# Rapide7seg.net
KiCad netlist of a schematic drawn in EAGLE
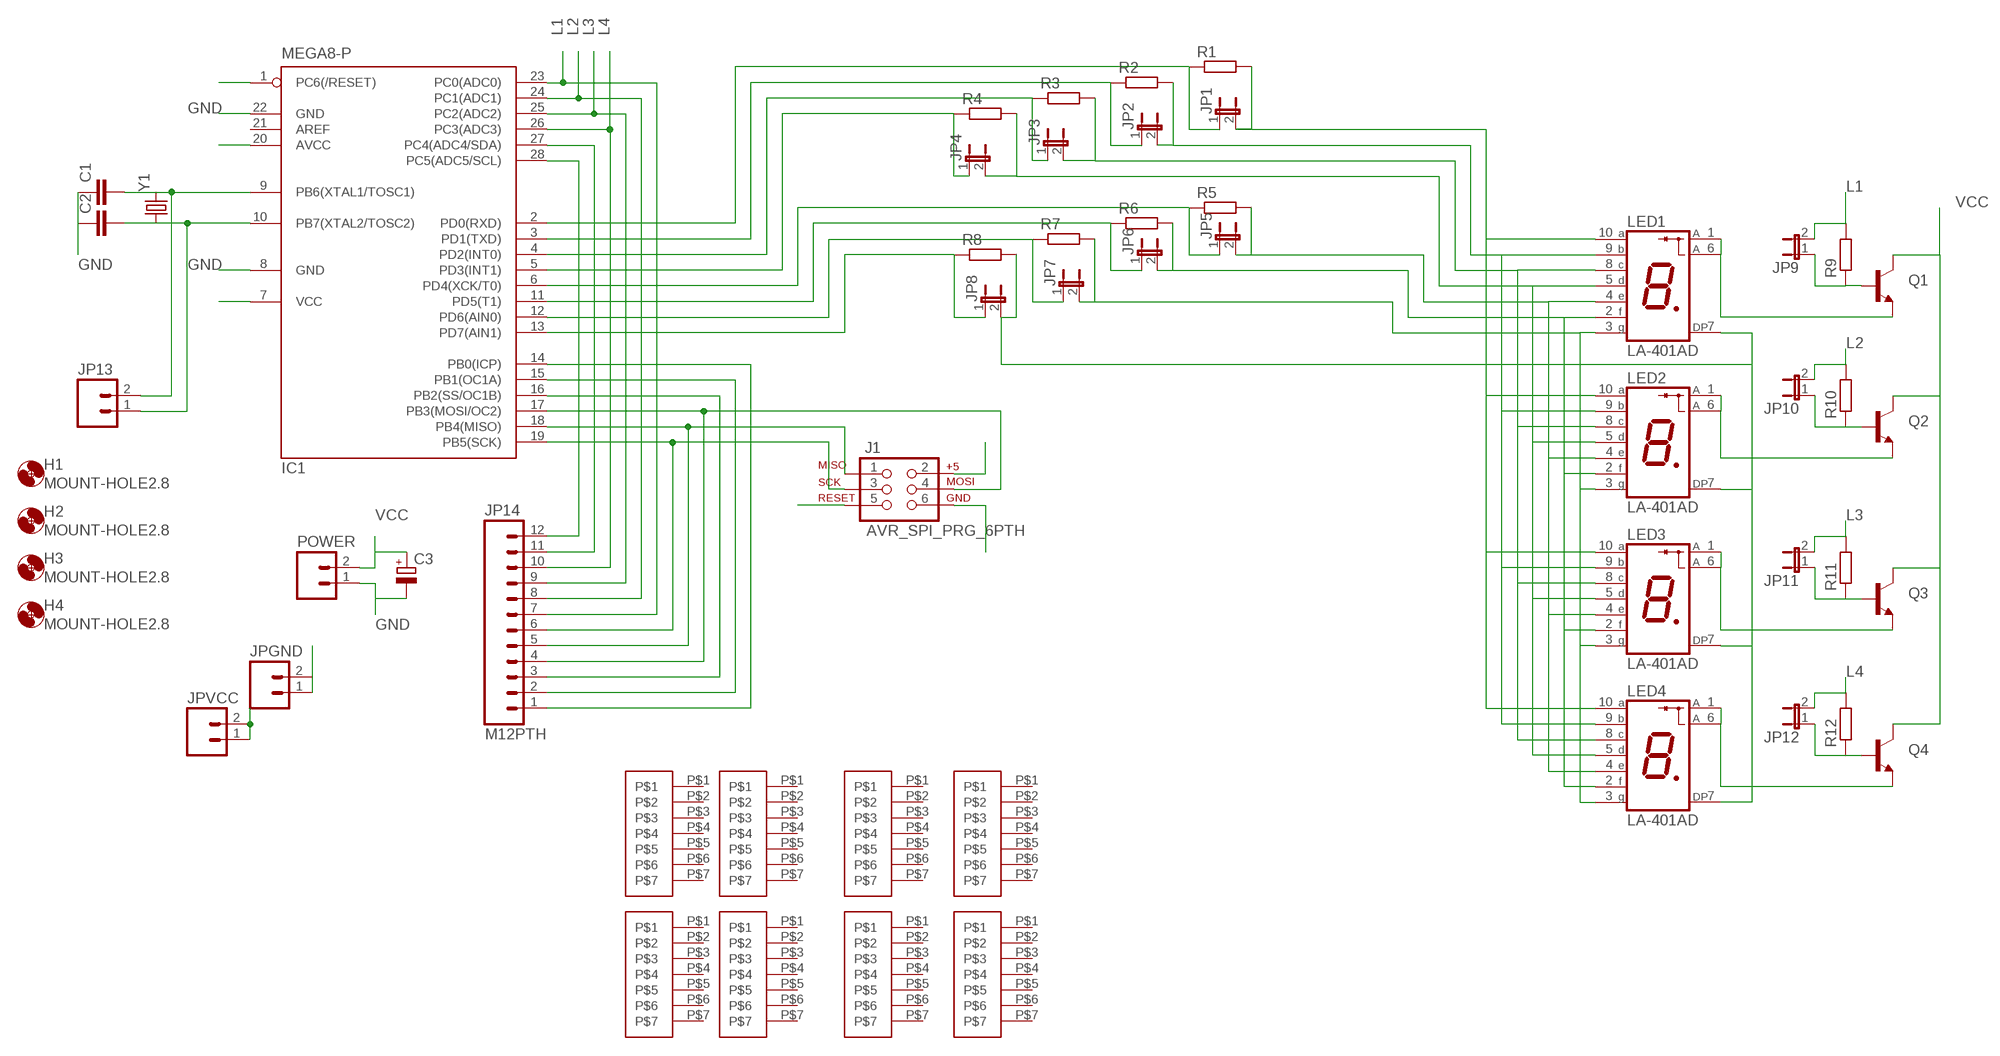
[diagram p0: schematic, sheet 1]

(export (version "E")
  (design (tool "Eeschema 10.0.6"))
  (components
    (comp (ref "C1")
      (value "C-EU025-024X044")
      (footprint "eagle-import:C025-024X044")
      (libsource (lib "eagle-import") (part "C-EU025-024X044"))
    )
    (comp (ref "C2")
      (value "C-EU025-024X044")
      (footprint "eagle-import:C025-024X044")
      (libsource (lib "eagle-import") (part "C-EU025-024X044"))
    )
    (comp (ref "C3")
      (value "CPOL-EUE1.8-4")
      (footprint "eagle-import:E1,8-4")
      (libsource (lib "eagle-import") (part "CPOL-EUE1.8-4"))
    )
    (comp (ref "H1")
      (value "MOUNT-HOLE2.8")
      (footprint "eagle-import:2,8")
      (libsource (lib "eagle-import") (part "MOUNT-HOLE2.8"))
    )
    (comp (ref "H2")
      (value "MOUNT-HOLE2.8")
      (footprint "eagle-import:2,8")
      (libsource (lib "eagle-import") (part "MOUNT-HOLE2.8"))
    )
    (comp (ref "H3")
      (value "MOUNT-HOLE2.8")
      (footprint "eagle-import:2,8")
      (libsource (lib "eagle-import") (part "MOUNT-HOLE2.8"))
    )
    (comp (ref "H4")
      (value "MOUNT-HOLE2.8")
      (footprint "eagle-import:2,8")
      (libsource (lib "eagle-import") (part "MOUNT-HOLE2.8"))
    )
    (comp (ref "IC1")
      (value "MEGA8-P")
      (footprint "eagle-import:DIL28-3")
      (libsource (lib "eagle-import") (part "MEGA8-P"))
    )
    (comp (ref "J1")
      (value "AVR_SPI_PRG_6PTH")
      (footprint "eagle-import:2X3")
      (libsource (lib "eagle-import") (part "AVR_SPI_PRG_6PTH"))
    )
    (comp (ref "JP1")
      (value "JUMPER-2SMD-NO")
      (footprint "eagle-import:SJ_2S-NO")
      (libsource (lib "eagle-import") (part "JUMPER-2SMD-NO"))
    )
    (comp (ref "JP2")
      (value "JUMPER-2SMD-NO")
      (footprint "eagle-import:SJ_2S-NO")
      (libsource (lib "eagle-import") (part "JUMPER-2SMD-NO"))
    )
    (comp (ref "JP3")
      (value "JUMPER-2SMD-NO")
      (footprint "eagle-import:SJ_2S-NO")
      (libsource (lib "eagle-import") (part "JUMPER-2SMD-NO"))
    )
    (comp (ref "JP4")
      (value "JUMPER-2SMD-NO")
      (footprint "eagle-import:SJ_2S-NO")
      (libsource (lib "eagle-import") (part "JUMPER-2SMD-NO"))
    )
    (comp (ref "JP5")
      (value "JUMPER-2SMD-NO")
      (footprint "eagle-import:SJ_2S-NO")
      (libsource (lib "eagle-import") (part "JUMPER-2SMD-NO"))
    )
    (comp (ref "JP6")
      (value "JUMPER-2SMD-NO")
      (footprint "eagle-import:SJ_2S-NO")
      (libsource (lib "eagle-import") (part "JUMPER-2SMD-NO"))
    )
    (comp (ref "JP7")
      (value "JUMPER-2SMD-NO")
      (footprint "eagle-import:SJ_2S-NO")
      (libsource (lib "eagle-import") (part "JUMPER-2SMD-NO"))
    )
    (comp (ref "JP8")
      (value "JUMPER-2SMD-NO")
      (footprint "eagle-import:SJ_2S-NO")
      (libsource (lib "eagle-import") (part "JUMPER-2SMD-NO"))
    )
    (comp (ref "JP9")
      (value "JUMPER-2SMD-NO")
      (footprint "eagle-import:SJ_2S-NO")
      (libsource (lib "eagle-import") (part "JUMPER-2SMD-NO"))
    )
    (comp (ref "JP10")
      (value "JUMPER-2SMD-NO")
      (footprint "eagle-import:SJ_2S-NO")
      (libsource (lib "eagle-import") (part "JUMPER-2SMD-NO"))
    )
    (comp (ref "JP11")
      (value "JUMPER-2SMD-NO")
      (footprint "eagle-import:SJ_2S-NO")
      (libsource (lib "eagle-import") (part "JUMPER-2SMD-NO"))
    )
    (comp (ref "JP12")
      (value "JUMPER-2SMD-NO")
      (footprint "eagle-import:SJ_2S-NO")
      (libsource (lib "eagle-import") (part "JUMPER-2SMD-NO"))
    )
    (comp (ref "JP13")
      (value "M02LOCK")
      (footprint "eagle-import:1X02_LOCK")
      (libsource (lib "eagle-import") (part "M02LOCK"))
    )
    (comp (ref "JP14")
      (value "M12PTH")
      (footprint "eagle-import:1X12")
      (libsource (lib "eagle-import") (part "M12PTH"))
    )
    (comp (ref "JPGND")
      (value "M02PTH")
      (footprint "eagle-import:1X02")
      (libsource (lib "eagle-import") (part "M02PTH"))
    )
    (comp (ref "JPVCC")
      (value "M02PTH")
      (footprint "eagle-import:1X02")
      (libsource (lib "eagle-import") (part "M02PTH"))
    )
    (comp (ref "LED1")
      (value "LA-401AD")
      (footprint "eagle-import:LA-401")
      (libsource (lib "eagle-import") (part "LA-401DA"))
    )
    (comp (ref "LED2")
      (value "LA-401AD")
      (footprint "eagle-import:LA-401")
      (libsource (lib "eagle-import") (part "LA-401DA"))
    )
    (comp (ref "LED3")
      (value "LA-401AD")
      (footprint "eagle-import:LA-401")
      (libsource (lib "eagle-import") (part "LA-401DA"))
    )
    (comp (ref "LED4")
      (value "LA-401AD")
      (footprint "eagle-import:LA-401")
      (libsource (lib "eagle-import") (part "LA-401DA"))
    )
    (comp (ref "POWER")
      (value "M02LOCK_LONGPADS")
      (footprint "eagle-import:1X02_LOCK_LONGPADS")
      (libsource (lib "eagle-import") (part "M02LOCK_LONGPADS"))
    )
    (comp (ref "Q1")
      (value "TRANSISTOR_NPNTO92")
      (footprint "eagle-import:TO-92")
      (libsource (lib "eagle-import") (part "TRANSISTOR_NPNTO92"))
    )
    (comp (ref "Q2")
      (value "TRANSISTOR_NPNTO92")
      (footprint "eagle-import:TO-92")
      (libsource (lib "eagle-import") (part "TRANSISTOR_NPNTO92"))
    )
    (comp (ref "Q3")
      (value "TRANSISTOR_NPNTO92")
      (footprint "eagle-import:TO-92")
      (libsource (lib "eagle-import") (part "TRANSISTOR_NPNTO92"))
    )
    (comp (ref "Q4")
      (value "TRANSISTOR_NPNTO92")
      (footprint "eagle-import:TO-92")
      (libsource (lib "eagle-import") (part "TRANSISTOR_NPNTO92"))
    )
    (comp (ref "R1")
      (value "R-EU_0204/7")
      (footprint "eagle-import:0204_7")
      (libsource (lib "eagle-import") (part "R-EU_0204/7"))
    )
    (comp (ref "R2")
      (value "R-EU_0204/7")
      (footprint "eagle-import:0204_7")
      (libsource (lib "eagle-import") (part "R-EU_0204/7"))
    )
    (comp (ref "R3")
      (value "R-EU_0204/7")
      (footprint "eagle-import:0204_7")
      (libsource (lib "eagle-import") (part "R-EU_0204/7"))
    )
    (comp (ref "R4")
      (value "R-EU_0204/7")
      (footprint "eagle-import:0204_7")
      (libsource (lib "eagle-import") (part "R-EU_0204/7"))
    )
    (comp (ref "R5")
      (value "R-EU_0204/7")
      (footprint "eagle-import:0204_7")
      (libsource (lib "eagle-import") (part "R-EU_0204/7"))
    )
    (comp (ref "R6")
      (value "R-EU_0204/7")
      (footprint "eagle-import:0204_7")
      (libsource (lib "eagle-import") (part "R-EU_0204/7"))
    )
    (comp (ref "R7")
      (value "R-EU_0204/7")
      (footprint "eagle-import:0204_7")
      (libsource (lib "eagle-import") (part "R-EU_0204/7"))
    )
    (comp (ref "R8")
      (value "R-EU_0204/7")
      (footprint "eagle-import:0204_7")
      (libsource (lib "eagle-import") (part "R-EU_0204/7"))
    )
    (comp (ref "R9")
      (value "R-EU_0204/7")
      (footprint "eagle-import:0204_7")
      (libsource (lib "eagle-import") (part "R-EU_0204/7"))
    )
    (comp (ref "R10")
      (value "R-EU_0204/7")
      (footprint "eagle-import:0204_7")
      (libsource (lib "eagle-import") (part "R-EU_0204/7"))
    )
    (comp (ref "R11")
      (value "R-EU_0204/7")
      (footprint "eagle-import:0204_7")
      (libsource (lib "eagle-import") (part "R-EU_0204/7"))
    )
    (comp (ref "R12")
      (value "R-EU_0204/7")
      (footprint "eagle-import:0204_7")
      (libsource (lib "eagle-import") (part "R-EU_0204/7"))
    )
    (comp (ref "U$1")
      (value "M7_NOSILK")
      (footprint "eagle-import:M7_NOSILK")
      (libsource (lib "eagle-import") (part "M7_NOSILK"))
    )
    (comp (ref "U$2")
      (value "M7_NOSILK")
      (footprint "eagle-import:M7_NOSILK")
      (libsource (lib "eagle-import") (part "M7_NOSILK"))
    )
    (comp (ref "U$3")
      (value "M7_NOSILK")
      (footprint "eagle-import:M7_NOSILK")
      (libsource (lib "eagle-import") (part "M7_NOSILK"))
    )
    (comp (ref "U$4")
      (value "M7_NOSILK")
      (footprint "eagle-import:M7_NOSILK")
      (libsource (lib "eagle-import") (part "M7_NOSILK"))
    )
    (comp (ref "U$5")
      (value "M7_NOSILK")
      (footprint "eagle-import:M7_NOSILK")
      (libsource (lib "eagle-import") (part "M7_NOSILK"))
    )
    (comp (ref "U$6")
      (value "M7_NOSILK")
      (footprint "eagle-import:M7_NOSILK")
      (libsource (lib "eagle-import") (part "M7_NOSILK"))
    )
    (comp (ref "U$7")
      (value "M7_NOSILK")
      (footprint "eagle-import:M7_NOSILK")
      (libsource (lib "eagle-import") (part "M7_NOSILK"))
    )
    (comp (ref "U$8")
      (value "M7_NOSILK")
      (footprint "eagle-import:M7_NOSILK")
      (libsource (lib "eagle-import") (part "M7_NOSILK"))
    )
    (comp (ref "Y1")
      (value "CRYSTALHC49UV")
      (footprint "eagle-import:HC49U-V")
      (libsource (lib "eagle-import") (part "CRYSTALHC49UV"))
    )
  )
  (nets
    (net (code "1") (name "/GND") (class "Default")
      (node (ref "C1") (pin "1") (pinfunction "1_1") (pintype "passive"))
      (node (ref "C2") (pin "1") (pinfunction "1_1") (pintype "passive"))
      (node (ref "C3") (pin "-") (pinfunction "-_-") (pintype "passive"))
      (node (ref "IC1") (pin "22") (pinfunction "GND_22") (pintype "power_in"))
      (node (ref "IC1") (pin "8") (pinfunction "GND_8") (pintype "power_in"))
      (node (ref "J1") (pin "6") (pinfunction "6_6") (pintype "passive"))
      (node (ref "JPGND") (pin "1") (pinfunction "1_1") (pintype "passive"))
      (node (ref "JPGND") (pin "2") (pinfunction "2_2") (pintype "passive"))
      (node (ref "POWER") (pin "1") (pinfunction "1_1") (pintype "passive"))
    )
    (net (code "2") (name "/L1") (class "Default")
      (node (ref "IC1") (pin "23") (pinfunction "PC0(ADC0)_23") (pintype "bidirectional"))
      (node (ref "JP14") (pin "7") (pinfunction "7_7") (pintype "passive"))
      (node (ref "JP9") (pin "2") (pinfunction "2_2") (pintype "passive"))
      (node (ref "R9") (pin "2") (pinfunction "2_2") (pintype "passive"))
    )
    (net (code "3") (name "/L2") (class "Default")
      (node (ref "IC1") (pin "24") (pinfunction "PC1(ADC1)_24") (pintype "bidirectional"))
      (node (ref "JP10") (pin "2") (pinfunction "2_2") (pintype "passive"))
      (node (ref "JP14") (pin "8") (pinfunction "8_8") (pintype "passive"))
      (node (ref "R10") (pin "2") (pinfunction "2_2") (pintype "passive"))
    )
    (net (code "4") (name "/L3") (class "Default")
      (node (ref "IC1") (pin "25") (pinfunction "PC2(ADC2)_25") (pintype "bidirectional"))
      (node (ref "JP11") (pin "2") (pinfunction "2_2") (pintype "passive"))
      (node (ref "JP14") (pin "9") (pinfunction "9_9") (pintype "passive"))
      (node (ref "R11") (pin "2") (pinfunction "2_2") (pintype "passive"))
    )
    (net (code "5") (name "/L4") (class "Default")
      (node (ref "IC1") (pin "26") (pinfunction "PC3(ADC3)_26") (pintype "bidirectional"))
      (node (ref "JP12") (pin "2") (pinfunction "2_2") (pintype "passive"))
      (node (ref "JP14") (pin "10") (pinfunction "10_10") (pintype "passive"))
      (node (ref "R12") (pin "2") (pinfunction "2_2") (pintype "passive"))
    )
    (net (code "6") (name "/UCRESET") (class "Default")
      (node (ref "IC1") (pin "1") (pinfunction "PC6(/RESET)_1") (pintype "bidirectional"))
      (node (ref "J1") (pin "5") (pinfunction "5_5") (pintype "passive"))
    )
    (net (code "7") (name "/VCC") (class "Default")
      (node (ref "C3") (pin "+") (pinfunction "+_+") (pintype "passive"))
      (node (ref "IC1") (pin "20") (pinfunction "AVCC_20") (pintype "power_in"))
      (node (ref "IC1") (pin "7") (pinfunction "VCC_7") (pintype "power_in"))
      (node (ref "J1") (pin "2") (pinfunction "2_2") (pintype "passive"))
      (node (ref "JPVCC") (pin "1") (pinfunction "1_1") (pintype "passive"))
      (node (ref "JPVCC") (pin "2") (pinfunction "2_2") (pintype "passive"))
      (node (ref "POWER") (pin "2") (pinfunction "2_2") (pintype "passive"))
      (node (ref "Q1") (pin "3") (pinfunction "C_3") (pintype "passive"))
      (node (ref "Q2") (pin "3") (pinfunction "C_3") (pintype "passive"))
      (node (ref "Q3") (pin "3") (pinfunction "C_3") (pintype "passive"))
      (node (ref "Q4") (pin "3") (pinfunction "C_3") (pintype "passive"))
    )
    (net (code "8") (name "Net-(IC1-PB0(ICP))") (class "Default")
      (node (ref "IC1") (pin "14") (pinfunction "PB0(ICP)_14") (pintype "bidirectional"))
      (node (ref "JP14") (pin "1") (pinfunction "1_1") (pintype "passive"))
    )
    (net (code "9") (name "Net-(IC1-PB1(OC1A))") (class "Default")
      (node (ref "IC1") (pin "15") (pinfunction "PB1(OC1A)_15") (pintype "bidirectional"))
      (node (ref "JP14") (pin "2") (pinfunction "2_2") (pintype "passive"))
    )
    (net (code "10") (name "Net-(IC1-PB2(SS{slash}OC1B))") (class "Default")
      (node (ref "IC1") (pin "16") (pinfunction "PB2(SS/OC1B)_16") (pintype "bidirectional"))
      (node (ref "JP14") (pin "3") (pinfunction "3_3") (pintype "passive"))
    )
    (net (code "11") (name "Net-(IC1-PB3(MOSI{slash}OC2))") (class "Default")
      (node (ref "IC1") (pin "17") (pinfunction "PB3(MOSI/OC2)_17") (pintype "bidirectional"))
      (node (ref "J1") (pin "4") (pinfunction "4_4") (pintype "passive"))
      (node (ref "JP14") (pin "4") (pinfunction "4_4") (pintype "passive"))
    )
    (net (code "12") (name "Net-(IC1-PB4(MISO))") (class "Default")
      (node (ref "IC1") (pin "18") (pinfunction "PB4(MISO)_18") (pintype "bidirectional"))
      (node (ref "J1") (pin "1") (pinfunction "1_1") (pintype "passive"))
      (node (ref "JP14") (pin "5") (pinfunction "5_5") (pintype "passive"))
    )
    (net (code "13") (name "Net-(IC1-PB5(SCK))") (class "Default")
      (node (ref "IC1") (pin "19") (pinfunction "PB5(SCK)_19") (pintype "bidirectional"))
      (node (ref "J1") (pin "3") (pinfunction "3_3") (pintype "passive"))
      (node (ref "JP14") (pin "6") (pinfunction "6_6") (pintype "passive"))
    )
    (net (code "14") (name "Net-(IC1-PB6(XTAL1{slash}TOSC1))") (class "Default")
      (node (ref "C1") (pin "2") (pinfunction "2_2") (pintype "passive"))
      (node (ref "IC1") (pin "9") (pinfunction "PB6(XTAL1/TOSC1)_9") (pintype "bidirectional"))
      (node (ref "JP13") (pin "2") (pinfunction "2_2") (pintype "passive"))
      (node (ref "Y1") (pin "2") (pinfunction "2_2") (pintype "passive"))
    )
    (net (code "15") (name "Net-(IC1-PB7(XTAL2{slash}TOSC2))") (class "Default")
      (node (ref "C2") (pin "2") (pinfunction "2_2") (pintype "passive"))
      (node (ref "IC1") (pin "10") (pinfunction "PB7(XTAL2/TOSC2)_10") (pintype "bidirectional"))
      (node (ref "JP13") (pin "1") (pinfunction "1_1") (pintype "passive"))
      (node (ref "Y1") (pin "1") (pinfunction "1_1") (pintype "passive"))
    )
    (net (code "16") (name "Net-(IC1-PC4(ADC4{slash}SDA))") (class "Default")
      (node (ref "IC1") (pin "27") (pinfunction "PC4(ADC4/SDA)_27") (pintype "bidirectional"))
      (node (ref "JP14") (pin "11") (pinfunction "11_11") (pintype "passive"))
    )
    (net (code "17") (name "Net-(IC1-PC5(ADC5{slash}SCL))") (class "Default")
      (node (ref "IC1") (pin "28") (pinfunction "PC5(ADC5/SCL)_28") (pintype "bidirectional"))
      (node (ref "JP14") (pin "12") (pinfunction "12_12") (pintype "passive"))
    )
    (net (code "18") (name "Net-(IC1-PD0(RXD))") (class "Default")
      (node (ref "IC1") (pin "2") (pinfunction "PD0(RXD)_2") (pintype "bidirectional"))
      (node (ref "JP1") (pin "1") (pinfunction "1_1") (pintype "passive"))
      (node (ref "R1") (pin "1") (pinfunction "1_1") (pintype "passive"))
    )
    (net (code "19") (name "Net-(IC1-PD1(TXD))") (class "Default")
      (node (ref "IC1") (pin "3") (pinfunction "PD1(TXD)_3") (pintype "bidirectional"))
      (node (ref "JP2") (pin "1") (pinfunction "1_1") (pintype "passive"))
      (node (ref "R2") (pin "1") (pinfunction "1_1") (pintype "passive"))
    )
    (net (code "20") (name "Net-(IC1-PD2(INT0))") (class "Default")
      (node (ref "IC1") (pin "4") (pinfunction "PD2(INT0)_4") (pintype "bidirectional"))
      (node (ref "JP3") (pin "1") (pinfunction "1_1") (pintype "passive"))
      (node (ref "R3") (pin "1") (pinfunction "1_1") (pintype "passive"))
    )
    (net (code "21") (name "Net-(IC1-PD3(INT1))") (class "Default")
      (node (ref "IC1") (pin "5") (pinfunction "PD3(INT1)_5") (pintype "bidirectional"))
      (node (ref "JP4") (pin "1") (pinfunction "1_1") (pintype "passive"))
      (node (ref "R4") (pin "1") (pinfunction "1_1") (pintype "passive"))
    )
    (net (code "22") (name "Net-(IC1-PD4(XCK{slash}T0))") (class "Default")
      (node (ref "IC1") (pin "6") (pinfunction "PD4(XCK/T0)_6") (pintype "bidirectional"))
      (node (ref "JP5") (pin "1") (pinfunction "1_1") (pintype "passive"))
      (node (ref "R5") (pin "1") (pinfunction "1_1") (pintype "passive"))
    )
    (net (code "23") (name "Net-(IC1-PD5(T1))") (class "Default")
      (node (ref "IC1") (pin "11") (pinfunction "PD5(T1)_11") (pintype "bidirectional"))
      (node (ref "JP6") (pin "1") (pinfunction "1_1") (pintype "passive"))
      (node (ref "R6") (pin "1") (pinfunction "1_1") (pintype "passive"))
    )
    (net (code "24") (name "Net-(IC1-PD6(AIN0))") (class "Default")
      (node (ref "IC1") (pin "12") (pinfunction "PD6(AIN0)_12") (pintype "bidirectional"))
      (node (ref "JP7") (pin "1") (pinfunction "1_1") (pintype "passive"))
      (node (ref "R7") (pin "1") (pinfunction "1_1") (pintype "passive"))
    )
    (net (code "25") (name "Net-(IC1-PD7(AIN1))") (class "Default")
      (node (ref "IC1") (pin "13") (pinfunction "PD7(AIN1)_13") (pintype "bidirectional"))
      (node (ref "JP8") (pin "1") (pinfunction "1_1") (pintype "passive"))
      (node (ref "R8") (pin "1") (pinfunction "1_1") (pintype "passive"))
    )
    (net (code "26") (name "Net-(JP1-Pad2)") (class "Default")
      (node (ref "JP1") (pin "2") (pinfunction "2_2") (pintype "passive"))
      (node (ref "LED1") (pin "10") (pinfunction "A_10") (pintype "passive"))
      (node (ref "LED2") (pin "10") (pinfunction "A_10") (pintype "passive"))
      (node (ref "LED3") (pin "10") (pinfunction "A_10") (pintype "passive"))
      (node (ref "LED4") (pin "10") (pinfunction "A_10") (pintype "passive"))
      (node (ref "R1") (pin "2") (pinfunction "2_2") (pintype "passive"))
    )
    (net (code "27") (name "Net-(LED1-B)") (class "Default")
      (node (ref "JP2") (pin "2") (pinfunction "2_2") (pintype "passive"))
      (node (ref "LED1") (pin "9") (pinfunction "B_9") (pintype "passive"))
      (node (ref "LED2") (pin "9") (pinfunction "B_9") (pintype "passive"))
      (node (ref "LED3") (pin "9") (pinfunction "B_9") (pintype "passive"))
      (node (ref "LED4") (pin "9") (pinfunction "B_9") (pintype "passive"))
      (node (ref "R2") (pin "2") (pinfunction "2_2") (pintype "passive"))
    )
    (net (code "28") (name "Net-(LED1-C)") (class "Default")
      (node (ref "JP3") (pin "2") (pinfunction "2_2") (pintype "passive"))
      (node (ref "LED1") (pin "8") (pinfunction "C_8") (pintype "passive"))
      (node (ref "LED2") (pin "8") (pinfunction "C_8") (pintype "passive"))
      (node (ref "LED3") (pin "8") (pinfunction "C_8") (pintype "passive"))
      (node (ref "LED4") (pin "8") (pinfunction "C_8") (pintype "passive"))
      (node (ref "R3") (pin "2") (pinfunction "2_2") (pintype "passive"))
    )
    (net (code "29") (name "Net-(LED1-D)") (class "Default")
      (node (ref "JP4") (pin "2") (pinfunction "2_2") (pintype "passive"))
      (node (ref "LED1") (pin "5") (pinfunction "D_5") (pintype "passive"))
      (node (ref "LED2") (pin "5") (pinfunction "D_5") (pintype "passive"))
      (node (ref "LED3") (pin "5") (pinfunction "D_5") (pintype "passive"))
      (node (ref "LED4") (pin "5") (pinfunction "D_5") (pintype "passive"))
      (node (ref "R4") (pin "2") (pinfunction "2_2") (pintype "passive"))
    )
    (net (code "30") (name "Net-(LED1-DP)") (class "Default")
      (node (ref "JP8") (pin "2") (pinfunction "2_2") (pintype "passive"))
      (node (ref "LED1") (pin "7") (pinfunction "DP_7") (pintype "passive"))
      (node (ref "LED2") (pin "7") (pinfunction "DP_7") (pintype "passive"))
      (node (ref "LED3") (pin "7") (pinfunction "DP_7") (pintype "passive"))
      (node (ref "LED4") (pin "7") (pinfunction "DP_7") (pintype "passive"))
      (node (ref "R8") (pin "2") (pinfunction "2_2") (pintype "passive"))
    )
    (net (code "31") (name "Net-(LED1-E)") (class "Default")
      (node (ref "JP5") (pin "2") (pinfunction "2_2") (pintype "passive"))
      (node (ref "LED1") (pin "4") (pinfunction "E_4") (pintype "passive"))
      (node (ref "LED2") (pin "4") (pinfunction "E_4") (pintype "passive"))
      (node (ref "LED3") (pin "4") (pinfunction "E_4") (pintype "passive"))
      (node (ref "LED4") (pin "4") (pinfunction "E_4") (pintype "passive"))
      (node (ref "R5") (pin "2") (pinfunction "2_2") (pintype "passive"))
    )
    (net (code "32") (name "Net-(LED1-F)") (class "Default")
      (node (ref "JP6") (pin "2") (pinfunction "2_2") (pintype "passive"))
      (node (ref "LED1") (pin "2") (pinfunction "F_2") (pintype "passive"))
      (node (ref "LED2") (pin "2") (pinfunction "F_2") (pintype "passive"))
      (node (ref "LED3") (pin "2") (pinfunction "F_2") (pintype "passive"))
      (node (ref "LED4") (pin "2") (pinfunction "F_2") (pintype "passive"))
      (node (ref "R6") (pin "2") (pinfunction "2_2") (pintype "passive"))
    )
    (net (code "33") (name "Net-(LED1-G)") (class "Default")
      (node (ref "JP7") (pin "2") (pinfunction "2_2") (pintype "passive"))
      (node (ref "LED1") (pin "3") (pinfunction "G_3") (pintype "passive"))
      (node (ref "LED2") (pin "3") (pinfunction "G_3") (pintype "passive"))
      (node (ref "LED3") (pin "3") (pinfunction "G_3") (pintype "passive"))
      (node (ref "LED4") (pin "3") (pinfunction "G_3") (pintype "passive"))
      (node (ref "R7") (pin "2") (pinfunction "2_2") (pintype "passive"))
    )
    (net (code "34") (name "Net-(Q1-B)") (class "Default")
      (node (ref "JP9") (pin "1") (pinfunction "1_1") (pintype "passive"))
      (node (ref "Q1") (pin "2") (pinfunction "B_2") (pintype "passive"))
      (node (ref "R9") (pin "1") (pinfunction "1_1") (pintype "passive"))
    )
    (net (code "35") (name "Net-(Q1-E)") (class "Default")
      (node (ref "LED1") (pin "1") (pinfunction "A_1") (pintype "passive"))
      (node (ref "LED1") (pin "6") (pinfunction "A_6") (pintype "passive"))
      (node (ref "Q1") (pin "1") (pinfunction "E_1") (pintype "passive"))
    )
    (net (code "36") (name "Net-(Q2-B)") (class "Default")
      (node (ref "JP10") (pin "1") (pinfunction "1_1") (pintype "passive"))
      (node (ref "Q2") (pin "2") (pinfunction "B_2") (pintype "passive"))
      (node (ref "R10") (pin "1") (pinfunction "1_1") (pintype "passive"))
    )
    (net (code "37") (name "Net-(Q2-E)") (class "Default")
      (node (ref "LED2") (pin "1") (pinfunction "A_1") (pintype "passive"))
      (node (ref "LED2") (pin "6") (pinfunction "A_6") (pintype "passive"))
      (node (ref "Q2") (pin "1") (pinfunction "E_1") (pintype "passive"))
    )
    (net (code "38") (name "Net-(Q3-B)") (class "Default")
      (node (ref "JP11") (pin "1") (pinfunction "1_1") (pintype "passive"))
      (node (ref "Q3") (pin "2") (pinfunction "B_2") (pintype "passive"))
      (node (ref "R11") (pin "1") (pinfunction "1_1") (pintype "passive"))
    )
    (net (code "39") (name "Net-(Q3-E)") (class "Default")
      (node (ref "LED3") (pin "1") (pinfunction "A_1") (pintype "passive"))
      (node (ref "LED3") (pin "6") (pinfunction "A_6") (pintype "passive"))
      (node (ref "Q3") (pin "1") (pinfunction "E_1") (pintype "passive"))
    )
    (net (code "40") (name "Net-(Q4-B)") (class "Default")
      (node (ref "JP12") (pin "1") (pinfunction "1_1") (pintype "passive"))
      (node (ref "Q4") (pin "2") (pinfunction "B_2") (pintype "passive"))
      (node (ref "R12") (pin "1") (pinfunction "1_1") (pintype "passive"))
    )
    (net (code "41") (name "Net-(Q4-E)") (class "Default")
      (node (ref "LED4") (pin "1") (pinfunction "A_1") (pintype "passive"))
      (node (ref "LED4") (pin "6") (pinfunction "A_6") (pintype "passive"))
      (node (ref "Q4") (pin "1") (pinfunction "E_1") (pintype "passive"))
    )
    (net (code "42") (name "unconnected-(IC1-AREF-Pad21)") (class "Default")
      (node (ref "IC1") (pin "21") (pinfunction "AREF_21") (pintype "passive"))
    )
    (net (code "43") (name "unconnected-(U$1-PadP$1)") (class "Default")
      (node (ref "U$1") (pin "P$1") (pinfunction "P$1_P$1") (pintype "bidirectional"))
    )
    (net (code "44") (name "unconnected-(U$1-PadP$2)") (class "Default")
      (node (ref "U$1") (pin "P$2") (pinfunction "P$2_P$2") (pintype "bidirectional"))
    )
    (net (code "45") (name "unconnected-(U$1-PadP$3)") (class "Default")
      (node (ref "U$1") (pin "P$3") (pinfunction "P$3_P$3") (pintype "bidirectional"))
    )
    (net (code "46") (name "unconnected-(U$1-PadP$4)") (class "Default")
      (node (ref "U$1") (pin "P$4") (pinfunction "P$4_P$4") (pintype "bidirectional"))
    )
    (net (code "47") (name "unconnected-(U$1-PadP$5)") (class "Default")
      (node (ref "U$1") (pin "P$5") (pinfunction "P$5_P$5") (pintype "bidirectional"))
    )
    (net (code "48") (name "unconnected-(U$1-PadP$6)") (class "Default")
      (node (ref "U$1") (pin "P$6") (pinfunction "P$6_P$6") (pintype "bidirectional"))
    )
    (net (code "49") (name "unconnected-(U$1-PadP$7)") (class "Default")
      (node (ref "U$1") (pin "P$7") (pinfunction "P$7_P$7") (pintype "bidirectional"))
    )
    (net (code "50") (name "unconnected-(U$2-PadP$1)") (class "Default")
      (node (ref "U$2") (pin "P$1") (pinfunction "P$1_P$1") (pintype "bidirectional"))
    )
    (net (code "51") (name "unconnected-(U$2-PadP$2)") (class "Default")
      (node (ref "U$2") (pin "P$2") (pinfunction "P$2_P$2") (pintype "bidirectional"))
    )
    (net (code "52") (name "unconnected-(U$2-PadP$3)") (class "Default")
      (node (ref "U$2") (pin "P$3") (pinfunction "P$3_P$3") (pintype "bidirectional"))
    )
    (net (code "53") (name "unconnected-(U$2-PadP$4)") (class "Default")
      (node (ref "U$2") (pin "P$4") (pinfunction "P$4_P$4") (pintype "bidirectional"))
    )
    (net (code "54") (name "unconnected-(U$2-PadP$5)") (class "Default")
      (node (ref "U$2") (pin "P$5") (pinfunction "P$5_P$5") (pintype "bidirectional"))
    )
    (net (code "55") (name "unconnected-(U$2-PadP$6)") (class "Default")
      (node (ref "U$2") (pin "P$6") (pinfunction "P$6_P$6") (pintype "bidirectional"))
    )
    (net (code "56") (name "unconnected-(U$2-PadP$7)") (class "Default")
      (node (ref "U$2") (pin "P$7") (pinfunction "P$7_P$7") (pintype "bidirectional"))
    )
    (net (code "57") (name "unconnected-(U$3-PadP$1)") (class "Default")
      (node (ref "U$3") (pin "P$1") (pinfunction "P$1_P$1") (pintype "bidirectional"))
    )
    (net (code "58") (name "unconnected-(U$3-PadP$2)") (class "Default")
      (node (ref "U$3") (pin "P$2") (pinfunction "P$2_P$2") (pintype "bidirectional"))
    )
    (net (code "59") (name "unconnected-(U$3-PadP$3)") (class "Default")
      (node (ref "U$3") (pin "P$3") (pinfunction "P$3_P$3") (pintype "bidirectional"))
    )
    (net (code "60") (name "unconnected-(U$3-PadP$4)") (class "Default")
      (node (ref "U$3") (pin "P$4") (pinfunction "P$4_P$4") (pintype "bidirectional"))
    )
    (net (code "61") (name "unconnected-(U$3-PadP$5)") (class "Default")
      (node (ref "U$3") (pin "P$5") (pinfunction "P$5_P$5") (pintype "bidirectional"))
    )
    (net (code "62") (name "unconnected-(U$3-PadP$6)") (class "Default")
      (node (ref "U$3") (pin "P$6") (pinfunction "P$6_P$6") (pintype "bidirectional"))
    )
    (net (code "63") (name "unconnected-(U$3-PadP$7)") (class "Default")
      (node (ref "U$3") (pin "P$7") (pinfunction "P$7_P$7") (pintype "bidirectional"))
    )
    (net (code "64") (name "unconnected-(U$4-PadP$1)") (class "Default")
      (node (ref "U$4") (pin "P$1") (pinfunction "P$1_P$1") (pintype "bidirectional"))
    )
    (net (code "65") (name "unconnected-(U$4-PadP$2)") (class "Default")
      (node (ref "U$4") (pin "P$2") (pinfunction "P$2_P$2") (pintype "bidirectional"))
    )
    (net (code "66") (name "unconnected-(U$4-PadP$3)") (class "Default")
      (node (ref "U$4") (pin "P$3") (pinfunction "P$3_P$3") (pintype "bidirectional"))
    )
    (net (code "67") (name "unconnected-(U$4-PadP$4)") (class "Default")
      (node (ref "U$4") (pin "P$4") (pinfunction "P$4_P$4") (pintype "bidirectional"))
    )
    (net (code "68") (name "unconnected-(U$4-PadP$5)") (class "Default")
      (node (ref "U$4") (pin "P$5") (pinfunction "P$5_P$5") (pintype "bidirectional"))
    )
    (net (code "69") (name "unconnected-(U$4-PadP$6)") (class "Default")
      (node (ref "U$4") (pin "P$6") (pinfunction "P$6_P$6") (pintype "bidirectional"))
    )
    (net (code "70") (name "unconnected-(U$4-PadP$7)") (class "Default")
      (node (ref "U$4") (pin "P$7") (pinfunction "P$7_P$7") (pintype "bidirectional"))
    )
    (net (code "71") (name "unconnected-(U$5-PadP$1)") (class "Default")
      (node (ref "U$5") (pin "P$1") (pinfunction "P$1_P$1") (pintype "bidirectional"))
    )
    (net (code "72") (name "unconnected-(U$5-PadP$2)") (class "Default")
      (node (ref "U$5") (pin "P$2") (pinfunction "P$2_P$2") (pintype "bidirectional"))
    )
    (net (code "73") (name "unconnected-(U$5-PadP$3)") (class "Default")
      (node (ref "U$5") (pin "P$3") (pinfunction "P$3_P$3") (pintype "bidirectional"))
    )
    (net (code "74") (name "unconnected-(U$5-PadP$4)") (class "Default")
      (node (ref "U$5") (pin "P$4") (pinfunction "P$4_P$4") (pintype "bidirectional"))
    )
    (net (code "75") (name "unconnected-(U$5-PadP$5)") (class "Default")
      (node (ref "U$5") (pin "P$5") (pinfunction "P$5_P$5") (pintype "bidirectional"))
    )
    (net (code "76") (name "unconnected-(U$5-PadP$6)") (class "Default")
      (node (ref "U$5") (pin "P$6") (pinfunction "P$6_P$6") (pintype "bidirectional"))
    )
    (net (code "77") (name "unconnected-(U$5-PadP$7)") (class "Default")
      (node (ref "U$5") (pin "P$7") (pinfunction "P$7_P$7") (pintype "bidirectional"))
    )
    (net (code "78") (name "unconnected-(U$6-PadP$1)") (class "Default")
      (node (ref "U$6") (pin "P$1") (pinfunction "P$1_P$1") (pintype "bidirectional"))
    )
    (net (code "79") (name "unconnected-(U$6-PadP$2)") (class "Default")
      (node (ref "U$6") (pin "P$2") (pinfunction "P$2_P$2") (pintype "bidirectional"))
    )
    (net (code "80") (name "unconnected-(U$6-PadP$3)") (class "Default")
      (node (ref "U$6") (pin "P$3") (pinfunction "P$3_P$3") (pintype "bidirectional"))
    )
    (net (code "81") (name "unconnected-(U$6-PadP$4)") (class "Default")
      (node (ref "U$6") (pin "P$4") (pinfunction "P$4_P$4") (pintype "bidirectional"))
    )
    (net (code "82") (name "unconnected-(U$6-PadP$5)") (class "Default")
      (node (ref "U$6") (pin "P$5") (pinfunction "P$5_P$5") (pintype "bidirectional"))
    )
    (net (code "83") (name "unconnected-(U$6-PadP$6)") (class "Default")
      (node (ref "U$6") (pin "P$6") (pinfunction "P$6_P$6") (pintype "bidirectional"))
    )
    (net (code "84") (name "unconnected-(U$6-PadP$7)") (class "Default")
      (node (ref "U$6") (pin "P$7") (pinfunction "P$7_P$7") (pintype "bidirectional"))
    )
    (net (code "85") (name "unconnected-(U$7-PadP$1)") (class "Default")
      (node (ref "U$7") (pin "P$1") (pinfunction "P$1_P$1") (pintype "bidirectional"))
    )
    (net (code "86") (name "unconnected-(U$7-PadP$2)") (class "Default")
      (node (ref "U$7") (pin "P$2") (pinfunction "P$2_P$2") (pintype "bidirectional"))
    )
    (net (code "87") (name "unconnected-(U$7-PadP$3)") (class "Default")
      (node (ref "U$7") (pin "P$3") (pinfunction "P$3_P$3") (pintype "bidirectional"))
    )
    (net (code "88") (name "unconnected-(U$7-PadP$4)") (class "Default")
      (node (ref "U$7") (pin "P$4") (pinfunction "P$4_P$4") (pintype "bidirectional"))
    )
    (net (code "89") (name "unconnected-(U$7-PadP$5)") (class "Default")
      (node (ref "U$7") (pin "P$5") (pinfunction "P$5_P$5") (pintype "bidirectional"))
    )
    (net (code "90") (name "unconnected-(U$7-PadP$6)") (class "Default")
      (node (ref "U$7") (pin "P$6") (pinfunction "P$6_P$6") (pintype "bidirectional"))
    )
    (net (code "91") (name "unconnected-(U$7-PadP$7)") (class "Default")
      (node (ref "U$7") (pin "P$7") (pinfunction "P$7_P$7") (pintype "bidirectional"))
    )
    (net (code "92") (name "unconnected-(U$8-PadP$1)") (class "Default")
      (node (ref "U$8") (pin "P$1") (pinfunction "P$1_P$1") (pintype "bidirectional"))
    )
    (net (code "93") (name "unconnected-(U$8-PadP$2)") (class "Default")
      (node (ref "U$8") (pin "P$2") (pinfunction "P$2_P$2") (pintype "bidirectional"))
    )
    (net (code "94") (name "unconnected-(U$8-PadP$3)") (class "Default")
      (node (ref "U$8") (pin "P$3") (pinfunction "P$3_P$3") (pintype "bidirectional"))
    )
    (net (code "95") (name "unconnected-(U$8-PadP$4)") (class "Default")
      (node (ref "U$8") (pin "P$4") (pinfunction "P$4_P$4") (pintype "bidirectional"))
    )
    (net (code "96") (name "unconnected-(U$8-PadP$5)") (class "Default")
      (node (ref "U$8") (pin "P$5") (pinfunction "P$5_P$5") (pintype "bidirectional"))
    )
    (net (code "97") (name "unconnected-(U$8-PadP$6)") (class "Default")
      (node (ref "U$8") (pin "P$6") (pinfunction "P$6_P$6") (pintype "bidirectional"))
    )
    (net (code "98") (name "unconnected-(U$8-PadP$7)") (class "Default")
      (node (ref "U$8") (pin "P$7") (pinfunction "P$7_P$7") (pintype "bidirectional"))
    )
  )
)
